# H-Bridge-Driver_V1_0.net
KiCad netlist of a schematic drawn in Altium Designer
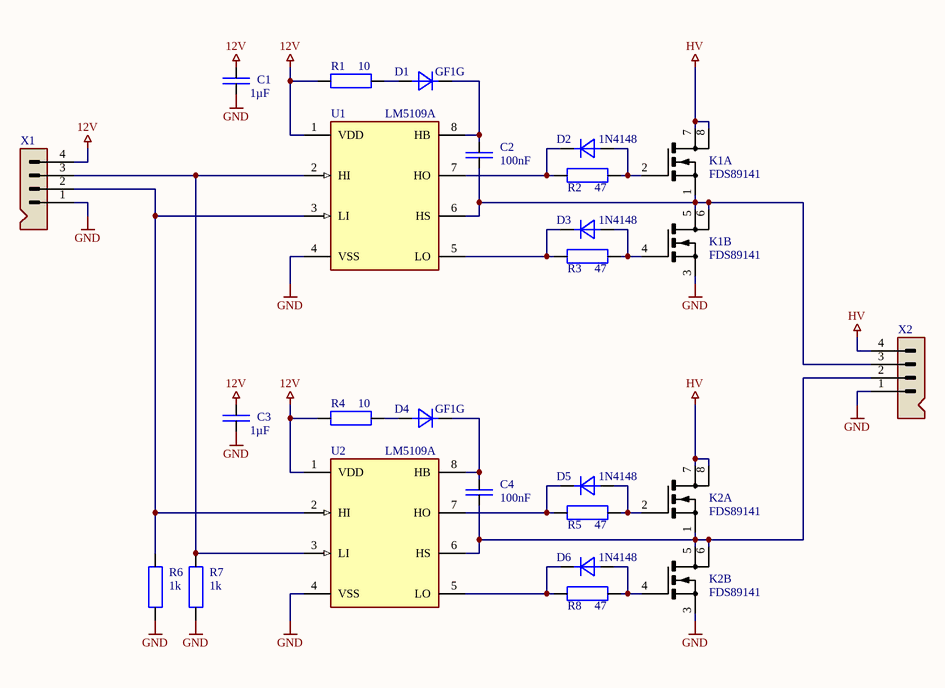
[diagram p0: H-Bridge-Driver_V1.0.SchDoc]

(export (version "E")
  (design (tool "Eeschema 10.0.6"))
  (components
    (comp (ref "C1")
      (value "1µF")
      (footprint "SMD Keramikkondensator 0603")
      (description "CAP-MK")
      (libsource (lib "AudioAmp") (part "C-CAPACITOR"))
    )
    (comp (ref "C2")
      (value "100nF")
      (footprint "SMD Keramikkondensator 0603")
      (description "CAP-MK")
      (libsource (lib "AudioAmp") (part "C-CAPACITOR"))
    )
    (comp (ref "C3")
      (value "1µF")
      (footprint "SMD Keramikkondensator 0603")
      (description "CAP-MK")
      (libsource (lib "AudioAmp") (part "C-CAPACITOR"))
    )
    (comp (ref "C4")
      (value "100nF")
      (footprint "SMD Keramikkondensator 0603")
      (description "CAP-MK")
      (libsource (lib "AudioAmp") (part "C-CAPACITOR"))
    )
    (comp (ref "D1")
      (value "GF1G")
      (footprint "SMD Diode DO-214-AC (SMA)")
      (description "DIODE (alt V)")
      (libsource (lib "TFS Integrated Library") (part "R-DIODE"))
    )
    (comp (ref "D2")
      (value "1N4148")
      (footprint "SMD Diode DO-213-AA")
      (description "DIODE (alt V)")
      (libsource (lib "TFS Integrated Library") (part "R-DIODE"))
    )
    (comp (ref "D3")
      (value "1N4148")
      (footprint "SMD Diode DO-213-AA")
      (description "DIODE (alt V)")
      (libsource (lib "TFS Integrated Library") (part "R-DIODE"))
    )
    (comp (ref "D4")
      (value "GF1G")
      (footprint "SMD Diode DO-214-AC (SMA)")
      (description "DIODE (alt V)")
      (libsource (lib "TFS Integrated Library") (part "R-DIODE"))
    )
    (comp (ref "D5")
      (value "1N4148")
      (footprint "SMD Diode DO-213-AA")
      (description "DIODE (alt V)")
      (libsource (lib "TFS Integrated Library") (part "R-DIODE"))
    )
    (comp (ref "D6")
      (value "1N4148")
      (footprint "SMD Diode DO-213-AA")
      (description "DIODE (alt V)")
      (libsource (lib "TFS Integrated Library") (part "R-DIODE"))
    )
    (comp (ref "K1")
      (value "FDS89141")
      (footprint "SMD IC SOIC-8")
      (description "Dual N-Channel MOSFET")
      (libsource (lib "H-Bridge-Driver") (part "K-FDS89141"))
    )
    (comp (ref "K2")
      (value "FDS89141")
      (footprint "SMD IC SOIC-8")
      (description "Dual N-Channel MOSFET")
      (libsource (lib "H-Bridge-Driver") (part "K-FDS89141"))
    )
    (comp (ref "R1")
      (value "10")
      (footprint "SMD Widerstand 0603")
      (description "RES (E=Heizwiderstand B=Messwandler)")
      (libsource (lib "") (part "R-RESISTOR_1"))
    )
    (comp (ref "R2")
      (value "47")
      (footprint "SMD Widerstand 0603")
      (description "RES (E=Heizwiderstand B=Messwandler)")
      (libsource (lib "") (part "R-RESISTOR_1"))
    )
    (comp (ref "R3")
      (value "47")
      (footprint "SMD Widerstand 0603")
      (description "RES (E=Heizwiderstand B=Messwandler)")
      (libsource (lib "") (part "R-RESISTOR_1"))
    )
    (comp (ref "R4")
      (value "10")
      (footprint "SMD Widerstand 0603")
      (description "RES (E=Heizwiderstand B=Messwandler)")
      (libsource (lib "") (part "R-RESISTOR_1"))
    )
    (comp (ref "R5")
      (value "47")
      (footprint "SMD Widerstand 0603")
      (description "RES (E=Heizwiderstand B=Messwandler)")
      (libsource (lib "") (part "R-RESISTOR_1"))
    )
    (comp (ref "R6")
      (value "1k")
      (footprint "SMD Widerstand 0603")
      (description "RES (E=Heizwiderstand B=Messwandler)")
      (libsource (lib "TFS Integrated Library") (part "R-RESISTOR"))
    )
    (comp (ref "R7")
      (value "1k")
      (footprint "SMD Widerstand 0603")
      (description "RES (E=Heizwiderstand B=Messwandler)")
      (libsource (lib "TFS Integrated Library") (part "R-RESISTOR"))
    )
    (comp (ref "R8")
      (value "47")
      (footprint "SMD Widerstand 0603")
      (description "RES (E=Heizwiderstand B=Messwandler)")
      (libsource (lib "") (part "R-RESISTOR_1"))
    )
    (comp (ref "U1")
      (value "LM5109A")
      (footprint "SMD IC SOIC-8")
      (description "High Voltage 1A Peak Half Bridge Gate Driver")
      (libsource (lib "H-Bridge-Driver") (part "U-LM5109A"))
    )
    (comp (ref "U2")
      (value "LM5109A")
      (footprint "SMD IC SOIC-8")
      (description "High Voltage 1A Peak Half Bridge Gate Driver")
      (libsource (lib "H-Bridge-Driver") (part "U-LM5109A"))
    )
    (comp (ref "X1")
      (value "Stiftleiste (4-Fach)")
      (footprint "THT Stiftleiste 1x4")
      (libsource (lib "H-Bridge-Driver") (part "X-Stiftleiste (4-Fach)"))
    )
    (comp (ref "X2")
      (value "Stiftleiste (4-Fach)")
      (footprint "THT Stiftleiste 1x4")
      (libsource (lib "") (part "X-Stiftleiste (4-Fach)_1"))
    )
  )
  (nets
    (net (code "1") (name "12V") (class "Default")
      (node (ref "C1") (pin "2") (pinfunction "2_2") (pintype "passive"))
      (node (ref "C3") (pin "2") (pinfunction "2_2") (pintype "passive"))
      (node (ref "R1") (pin "2") (pinfunction "2_2") (pintype "passive"))
      (node (ref "R4") (pin "2") (pinfunction "2_2") (pintype "passive"))
      (node (ref "U1") (pin "1") (pinfunction "VDD_1") (pintype "power_in"))
      (node (ref "U2") (pin "1") (pinfunction "VDD_1") (pintype "power_in"))
      (node (ref "X1") (pin "4") (pinfunction "4_4") (pintype "passive"))
    )
    (net (code "2") (name "GND") (class "Default")
      (node (ref "C1") (pin "1") (pinfunction "1_1") (pintype "passive"))
      (node (ref "C3") (pin "1") (pinfunction "1_1") (pintype "passive"))
      (node (ref "K1") (pin "3") (pinfunction "S2_3") (pintype "passive"))
      (node (ref "K2") (pin "3") (pinfunction "S2_3") (pintype "passive"))
      (node (ref "R6") (pin "1") (pinfunction "1_1") (pintype "passive"))
      (node (ref "R7") (pin "1") (pinfunction "1_1") (pintype "passive"))
      (node (ref "U1") (pin "4") (pinfunction "VSS_4") (pintype "power_in"))
      (node (ref "U2") (pin "4") (pinfunction "VSS_4") (pintype "power_in"))
      (node (ref "X1") (pin "1") (pinfunction "1_1") (pintype "passive"))
      (node (ref "X2") (pin "1") (pinfunction "1_1") (pintype "passive"))
    )
    (net (code "3") (name "HV") (class "Default")
      (node (ref "K1") (pin "7") (pinfunction "D1_7") (pintype "passive"))
      (node (ref "K1") (pin "8") (pinfunction "D1_8") (pintype "passive"))
      (node (ref "K2") (pin "7") (pinfunction "D1_7") (pintype "passive"))
      (node (ref "K2") (pin "8") (pinfunction "D1_8") (pintype "passive"))
      (node (ref "X2") (pin "4") (pinfunction "4_4") (pintype "passive"))
    )
    (net (code "4") (name "Net-(D1-PadA)") (class "Default")
      (node (ref "D1") (pin "A") (pinfunction "A_A") (pintype "passive"))
      (node (ref "R1") (pin "1") (pinfunction "1_1") (pintype "passive"))
    )
    (net (code "5") (name "Net-(D4-PadA)") (class "Default")
      (node (ref "D4") (pin "A") (pinfunction "A_A") (pintype "passive"))
      (node (ref "R4") (pin "1") (pinfunction "1_1") (pintype "passive"))
    )
    (net (code "6") (name "Net-(K1A-G1)") (class "Default")
      (node (ref "D2") (pin "A") (pinfunction "A_A") (pintype "passive"))
      (node (ref "K1") (pin "2") (pinfunction "G1_2") (pintype "passive"))
      (node (ref "R2") (pin "1") (pinfunction "1_1") (pintype "passive"))
    )
    (net (code "7") (name "Net-(K1A-S1)") (class "Default")
      (node (ref "C2") (pin "1") (pinfunction "1_1") (pintype "passive"))
      (node (ref "K1") (pin "1") (pinfunction "S1_1") (pintype "passive"))
      (node (ref "K1") (pin "5") (pinfunction "D2_5") (pintype "passive"))
      (node (ref "K1") (pin "6") (pinfunction "D2_6") (pintype "passive"))
      (node (ref "U1") (pin "6") (pinfunction "HS_6") (pintype "passive"))
      (node (ref "X2") (pin "3") (pinfunction "3_3") (pintype "passive"))
    )
    (net (code "8") (name "Net-(K1B-G2)") (class "Default")
      (node (ref "D3") (pin "A") (pinfunction "A_A") (pintype "passive"))
      (node (ref "K1") (pin "4") (pinfunction "G2_4") (pintype "passive"))
      (node (ref "R3") (pin "1") (pinfunction "1_1") (pintype "passive"))
    )
    (net (code "9") (name "Net-(K2A-G1)") (class "Default")
      (node (ref "D5") (pin "A") (pinfunction "A_A") (pintype "passive"))
      (node (ref "K2") (pin "2") (pinfunction "G1_2") (pintype "passive"))
      (node (ref "R5") (pin "1") (pinfunction "1_1") (pintype "passive"))
    )
    (net (code "10") (name "Net-(K2A-S1)") (class "Default")
      (node (ref "C4") (pin "1") (pinfunction "1_1") (pintype "passive"))
      (node (ref "K2") (pin "1") (pinfunction "S1_1") (pintype "passive"))
      (node (ref "K2") (pin "5") (pinfunction "D2_5") (pintype "passive"))
      (node (ref "K2") (pin "6") (pinfunction "D2_6") (pintype "passive"))
      (node (ref "U2") (pin "6") (pinfunction "HS_6") (pintype "passive"))
      (node (ref "X2") (pin "2") (pinfunction "2_2") (pintype "passive"))
    )
    (net (code "11") (name "Net-(K2B-G2)") (class "Default")
      (node (ref "D6") (pin "A") (pinfunction "A_A") (pintype "passive"))
      (node (ref "K2") (pin "4") (pinfunction "G2_4") (pintype "passive"))
      (node (ref "R8") (pin "1") (pinfunction "1_1") (pintype "passive"))
    )
    (net (code "12") (name "Net-(U1-HB)") (class "Default")
      (node (ref "C2") (pin "2") (pinfunction "2_2") (pintype "passive"))
      (node (ref "D1") (pin "K") (pinfunction "K_K") (pintype "passive"))
      (node (ref "U1") (pin "8") (pinfunction "HB_8") (pintype "passive"))
    )
    (net (code "13") (name "Net-(U1-HI)") (class "Default")
      (node (ref "R7") (pin "2") (pinfunction "2_2") (pintype "passive"))
      (node (ref "U1") (pin "2") (pinfunction "HI_2") (pintype "input"))
      (node (ref "U2") (pin "3") (pinfunction "LI_3") (pintype "input"))
      (node (ref "X1") (pin "3") (pinfunction "3_3") (pintype "passive"))
    )
    (net (code "14") (name "Net-(U1-HO)") (class "Default")
      (node (ref "D2") (pin "K") (pinfunction "K_K") (pintype "passive"))
      (node (ref "R2") (pin "2") (pinfunction "2_2") (pintype "passive"))
      (node (ref "U1") (pin "7") (pinfunction "HO_7") (pintype "passive"))
    )
    (net (code "15") (name "Net-(U1-LI)") (class "Default")
      (node (ref "R6") (pin "2") (pinfunction "2_2") (pintype "passive"))
      (node (ref "U1") (pin "3") (pinfunction "LI_3") (pintype "input"))
      (node (ref "U2") (pin "2") (pinfunction "HI_2") (pintype "input"))
      (node (ref "X1") (pin "2") (pinfunction "2_2") (pintype "passive"))
    )
    (net (code "16") (name "Net-(U1-LO)") (class "Default")
      (node (ref "D3") (pin "K") (pinfunction "K_K") (pintype "passive"))
      (node (ref "R3") (pin "2") (pinfunction "2_2") (pintype "passive"))
      (node (ref "U1") (pin "5") (pinfunction "LO_5") (pintype "passive"))
    )
    (net (code "17") (name "Net-(U2-HB)") (class "Default")
      (node (ref "C4") (pin "2") (pinfunction "2_2") (pintype "passive"))
      (node (ref "D4") (pin "K") (pinfunction "K_K") (pintype "passive"))
      (node (ref "U2") (pin "8") (pinfunction "HB_8") (pintype "passive"))
    )
    (net (code "18") (name "Net-(U2-HO)") (class "Default")
      (node (ref "D5") (pin "K") (pinfunction "K_K") (pintype "passive"))
      (node (ref "R5") (pin "2") (pinfunction "2_2") (pintype "passive"))
      (node (ref "U2") (pin "7") (pinfunction "HO_7") (pintype "passive"))
    )
    (net (code "19") (name "Net-(U2-LO)") (class "Default")
      (node (ref "D6") (pin "K") (pinfunction "K_K") (pintype "passive"))
      (node (ref "R8") (pin "2") (pinfunction "2_2") (pintype "passive"))
      (node (ref "U2") (pin "5") (pinfunction "LO_5") (pintype "passive"))
    )
  )
)
